# Power.net
KiCad netlist of a schematic drawn in Altium Designer
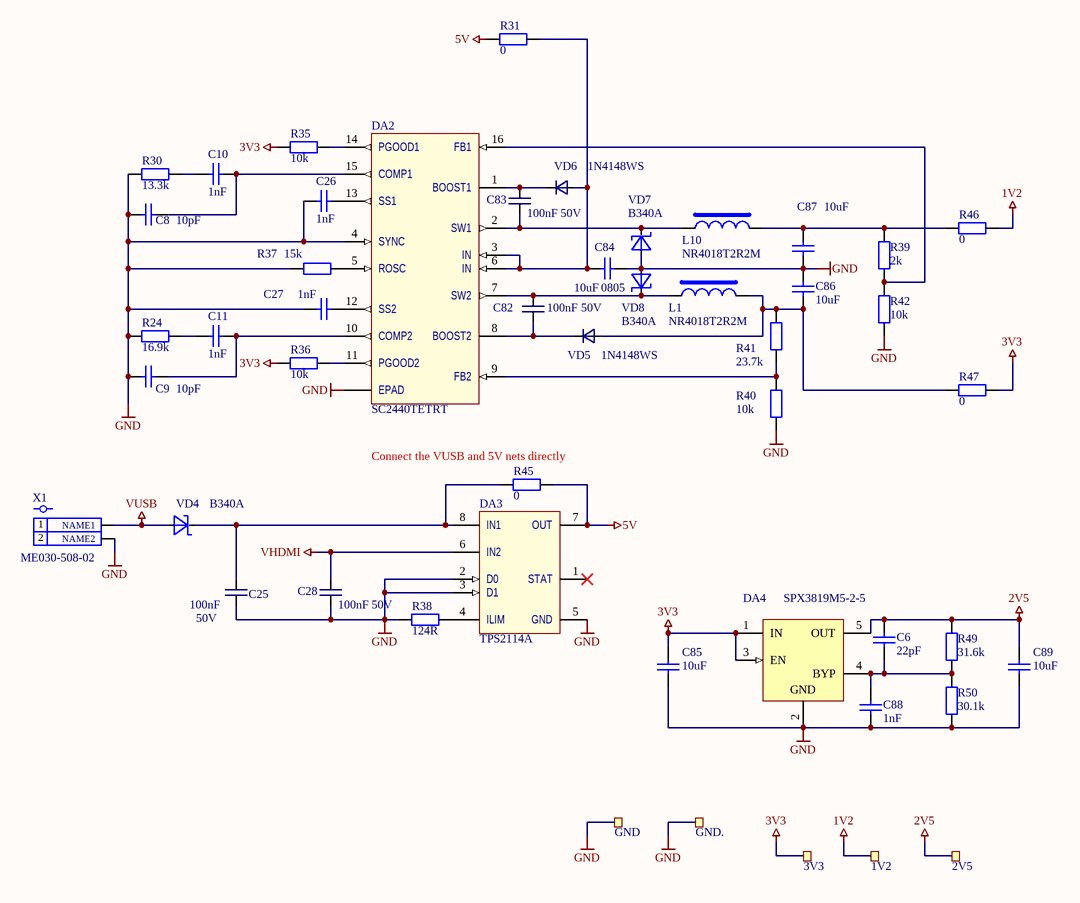
[diagram p0: Power.SchDoc]

(export (version "E")
  (design (tool "Eeschema 10.0.6"))
  (components
    (comp (ref "1V2")
      (value "TP_TH")
      (footprint "TP_TH_1MM")
      (description "Testpoint, through hole")
      (libsource (lib "LED_MAT_3") (part "TESTPAD_TH"))
    )
    (comp (ref "2V5")
      (value "Ø1.0mm,SMD")
      (footprint "TP_SMD_1MM")
      (description "circular SMD testpad 1mm")
      (libsource (lib "LED_MAT_3") (part "TESTPAD_SMD"))
    )
    (comp (ref "3V3")
      (value "TP_TH")
      (footprint "TP_TH_1MM")
      (description "Testpoint, through hole")
      (libsource (lib "LED_MAT_3") (part "TESTPAD_TH"))
    )
    (comp (ref "C6")
      (value "22pF")
      (footprint "CAPC1608L")
      (description "Capacitor ceramic")
      (fields
        (field (name "MANUFACTURER") "SAMSUNG")
        (field (name "MANUFACTURER PART NUMBER") "CL10C100JB8NNNC")
      )
      (libsource (lib "LED_MAT_3") (part "10pF / 0603 / COG / 50V"))
    )
    (comp (ref "C8")
      (value "10pF")
      (footprint "CAPC1608L")
      (description "Capacitor ceramic")
      (fields
        (field (name "MANUFACTURER") "SAMSUNG")
        (field (name "MANUFACTURER PART NUMBER") "CL10C100JB8NNNC")
      )
      (libsource (lib "LED_MAT_3") (part "10pF / 0603 / COG / 50V"))
    )
    (comp (ref "C9")
      (value "10pF")
      (footprint "CAPC1608L")
      (description "Capacitor ceramic")
      (fields
        (field (name "MANUFACTURER") "SAMSUNG")
        (field (name "MANUFACTURER PART NUMBER") "CL10C100JB8NNNC")
      )
      (libsource (lib "LED_MAT_3") (part "10pF / 0603 / COG / 50V"))
    )
    (comp (ref "C10")
      (value "1nF")
      (footprint "CAPC1608L")
      (description "Capacitor ceramic")
      (fields
        (field (name "MANUFACTURER") "MURATA")
        (field (name "MANUFACTURER PART NUMBER") "GRM1885C1H102JA01D")
      )
      (libsource (lib "LED_MAT_3") (part "1nF / 0603 / NPO / 50V"))
    )
    (comp (ref "C11")
      (value "1nF")
      (footprint "CAPC1608L")
      (description "Capacitor ceramic")
      (fields
        (field (name "MANUFACTURER") "MURATA")
        (field (name "MANUFACTURER PART NUMBER") "GRM1885C1H102JA01D")
      )
      (libsource (lib "LED_MAT_3") (part "1nF / 0603 / NPO / 50V"))
    )
    (comp (ref "C25")
      (value "100nF")
      (footprint "CAPC1608L")
      (description "Capacitor SMD")
      (fields
        (field (name "VOLTAGE") "50V")
        (field (name "TOLERANCE") "5%")
        (field (name "MANUFACTURER") "SAMSUNG")
      )
      (libsource (lib "LED_MAT_3") (part "Capacitor CC0805 100nF C0G"))
    )
    (comp (ref "C26")
      (value "1nF")
      (footprint "CAPC1608L")
      (description "Capacitor ceramic")
      (fields
        (field (name "MANUFACTURER") "MURATA")
        (field (name "MANUFACTURER PART NUMBER") "GRM1885C1H102JA01D")
      )
      (libsource (lib "LED_MAT_3") (part "1nF / 0603 / NPO / 50V"))
    )
    (comp (ref "C27")
      (value "1nF")
      (footprint "CAPC1608L")
      (description "Capacitor ceramic")
      (fields
        (field (name "MANUFACTURER") "MURATA")
        (field (name "MANUFACTURER PART NUMBER") "GRM1885C1H102JA01D")
      )
      (libsource (lib "LED_MAT_3") (part "1nF / 0603 / NPO / 50V"))
    )
    (comp (ref "C28")
      (value "100nF")
      (footprint "CAPC1608L")
      (description "Capacitor SMD")
      (fields
        (field (name "VOLTAGE") "50V")
        (field (name "TOLERANCE") "5%")
        (field (name "MANUFACTURER") "SAMSUNG")
      )
      (libsource (lib "LED_MAT_3") (part "Capacitor CC0805 100nF C0G"))
    )
    (comp (ref "C82")
      (value "100nF")
      (footprint "CAPC1608L")
      (description "Capacitor SMD")
      (fields
        (field (name "VOLTAGE") "50V")
        (field (name "TOLERANCE") "5%")
        (field (name "MANUFACTURER") "SAMSUNG")
      )
      (libsource (lib "LED_MAT_3") (part "Capacitor CC0805 100nF C0G"))
    )
    (comp (ref "C83")
      (value "100nF")
      (footprint "CAPC1608L")
      (description "Capacitor SMD")
      (fields
        (field (name "VOLTAGE") "50V")
        (field (name "TOLERANCE") "5%")
        (field (name "MANUFACTURER") "SAMSUNG")
      )
      (libsource (lib "LED_MAT_3") (part "Capacitor CC0805 100nF C0G"))
    )
    (comp (ref "C84")
      (value "10uF")
      (footprint "CAPC2012L")
      (description "Capacitor ceramic")
      (fields
        (field (name "PACKAGE") "0805")
        (field (name "VOLTAGE") "10V")
        (field (name "Comment") "10uF / 0805 /  X5R / 10V")
      )
      (libsource (lib "LED_MAT_3") (part "10uF / 0805 /  X5R / 10V"))
    )
    (comp (ref "C85")
      (value "10uF")
      (footprint "CAPC2012L")
      (description "Capacitor ceramic")
      (fields (field (name "VOLTAGE") "10V") (field (name "Comment") "10uF / 0805 /  X5R / 10V"))
      (libsource (lib "LED_MAT_3") (part "10uF / 0805 /  X5R / 10V"))
    )
    (comp (ref "C86")
      (value "10uF")
      (footprint "CAPC2012L")
      (description "Capacitor ceramic")
      (fields (field (name "VOLTAGE") "10V") (field (name "Comment") "10uF / 0805 /  X5R / 10V"))
      (libsource (lib "LED_MAT_3") (part "10uF / 0805 /  X5R / 10V"))
    )
    (comp (ref "C87")
      (value "10uF")
      (footprint "CAPC2012L")
      (description "Capacitor ceramic")
      (fields (field (name "VOLTAGE") "10V") (field (name "Comment") "10uF / 0805 /  X5R / 10V"))
      (libsource (lib "LED_MAT_3") (part "10uF / 0805 /  X5R / 10V"))
    )
    (comp (ref "C88")
      (value "1nF")
      (footprint "CAPC1608L")
      (description "Capacitor ceramic")
      (fields
        (field (name "MANUFACTURER") "MURATA")
        (field (name "MANUFACTURER PART NUMBER") "GRM1885C1H102JA01D")
      )
      (libsource (lib "LED_MAT_3") (part "1nF / 0603 / NPO / 50V"))
    )
    (comp (ref "C89")
      (value "10uF")
      (footprint "CAPC2012L")
      (description "Capacitor ceramic")
      (fields (field (name "VOLTAGE") "10V") (field (name "Comment") "10uF / 0805 /  X5R / 10V"))
      (libsource (lib "LED_MAT_3") (part "10uF / 0805 /  X5R / 10V"))
    )
    (comp (ref "DA2")
      (value "SC2440TETRT")
      (footprint "TSOP65P640X110_HS320X320-16L")
      (description "2.5 MHz Dual Switching Regulator, 2A")
      (fields (field (name "MANUFACTURER") "SEMTECH"))
      (libsource (lib "power") (part "SC2440"))
    )
    (comp (ref "DA3")
      (value "TPS2114A")
      (footprint "TSSOP65P640X120-8L")
      (description "AUTOSWITCHING POWER MUX")
      (fields (field (name "MANUFACTURER") "TI"))
      (libsource (lib "LED_MAT_3") (part "TPS2114A"))
    )
    (comp (ref "DA4")
      (value "SPX3819M5-2-5")
      (footprint "TI-DBV6_N")
      (description "500mA, Low-Noise LDO Voltage Regulator")
      (fields (field (name "MANUFACTURER") "SIPEX") (field (name "TOLERANCE") "1%"))
      (libsource (lib "LED_MAT_3") (part "SPX3819M5-2-5"))
    )
    (comp (ref "GND")
      (value "TP_TH")
      (footprint "TP_TH_1MM")
      (description "Testpoint, through hole")
      (libsource (lib "LED_MAT_3") (part "TESTPAD_TH"))
    )
    (comp (ref "GND.")
      (value "TP_TH")
      (footprint "TP_TH_1MM")
      (description "Testpoint, through hole")
      (libsource (lib "LED_MAT_3") (part "TESTPAD_TH"))
    )
    (comp (ref "L1")
      (value "NR4018T2R2M")
      (footprint "IND_CD43")
      (description "Power choke")
      (fields (field (name "MANUFACTURER") "TAIYO YUDE"))
      (libsource (lib "LED_MAT_3") (part "2.2uH Power Choke"))
    )
    (comp (ref "L10")
      (value "NR4018T2R2M")
      (footprint "IND_CD43")
      (description "Power choke")
      (fields (field (name "MANUFACTURER") "TAIYO YUDE"))
      (libsource (lib "LED_MAT_3") (part "2.2uH Power Choke"))
    )
    (comp (ref "R24")
      (value "16.9k")
      (footprint "RESC1608L")
      (description "16.9k / 1% / 0603")
      (fields
        (field (name "MANUFACTURER") "YAGEO")
        (field (name "MANUFACTURER PART NUMBER") "RC0603FR0716K9L")
      )
      (libsource (lib "LED_MAT_3") (part "16.9k / 1% / 0603"))
    )
    (comp (ref "R30")
      (value "13.3k")
      (footprint "RESC1608L")
      (description "13.3k / 1% / 0603")
      (fields
        (field (name "MANUFACTURER") "YAGEO")
        (field (name "MANUFACTURER PART NUMBER") "RC0603FR-0713K3L")
      )
      (libsource (lib "LED_MAT_3") (part "13.3k / 1% / 0603"))
    )
    (comp (ref "R31")
      (value "0")
      (footprint "RESC3216L")
      (description "0 / 1% / 0603")
      (fields
        (field (name "MANUFACTURER") "YAGEO")
        (field (name "MANUFACTURER PART NUMBER") "RC0603FR-070RL")
      )
      (libsource (lib "LED_MAT_3") (part "2k / 1% / 0603"))
    )
    (comp (ref "R35")
      (value "10k")
      (footprint "RESC1608L")
      (description "Resistor")
      (fields (field (name "TOLERANCE") "1%") (field (name "VOLTAGE") "50V"))
      (libsource (lib "") (part "10k / 1% / 0603 / TC100 / 50V / 0.1W_1"))
    )
    (comp (ref "R36")
      (value "10k")
      (footprint "RESC1608L")
      (description "Resistor")
      (fields (field (name "TOLERANCE") "1%") (field (name "VOLTAGE") "50V"))
      (libsource (lib "") (part "10k / 1% / 0603 / TC100 / 50V / 0.1W_1"))
    )
    (comp (ref "R37")
      (value "15k")
      (footprint "RESC1608L")
      (description "15k / 1% / 0603")
      (fields
        (field (name "MANUFACTURER") "YAGEO")
        (field (name "MANUFACTURER PART NUMBER") "RC0603FR-0715KL")
      )
      (libsource (lib "LED_MAT_3") (part "15k / 1% / 0603"))
    )
    (comp (ref "R38")
      (value "124R")
      (footprint "RESC1608L")
      (description "124R / 1% / 0603")
      (fields
        (field (name "MANUFACTURER") "PANASONIC")
        (field (name "MANUFACTURER PART NUMBER") "ERJ-3EKF1240V")
      )
      (libsource (lib "") (part "124R / 1% / 0603_1"))
    )
    (comp (ref "R39")
      (value "2k")
      (footprint "RESC1608L")
      (description "2k / 1% / 0603")
      (fields
        (field (name "MANUFACTURER") "YAGEO")
        (field (name "MANUFACTURER PART NUMBER") "RC0603FR-072KL")
      )
      (libsource (lib "") (part "2k / 1% / 0603_1"))
    )
    (comp (ref "R40")
      (value "10k")
      (footprint "RESC1608L")
      (description "Resistor")
      (fields (field (name "TOLERANCE") "1%") (field (name "VOLTAGE") "50V"))
      (libsource (lib "LED_MAT_3") (part "10k / 1% / 0603 / TC100 / 50V / 0.1W"))
    )
    (comp (ref "R41")
      (value "23.7k")
      (footprint "RESC1608L")
      (description "23.7k / 1% / 0603")
      (fields
        (field (name "MANUFACTURER") "YAGEO")
        (field (name "MANUFACTURER PART NUMBER") "RC0603FR-0723K7L")
      )
      (libsource (lib "LED_MAT_3") (part "23.7k / 1% / 0603"))
    )
    (comp (ref "R42")
      (value "10k")
      (footprint "RESC1608L")
      (description "Resistor")
      (fields (field (name "TOLERANCE") "1%") (field (name "VOLTAGE") "50V"))
      (libsource (lib "LED_MAT_3") (part "10k / 1% / 0603 / TC100 / 50V / 0.1W"))
    )
    (comp (ref "R45")
      (value "0")
      (footprint "RESC1608L")
      (description "0 / 1% / 0603")
      (fields
        (field (name "MANUFACTURER") "YAGEO")
        (field (name "MANUFACTURER PART NUMBER") "RC0603FR-070RL")
      )
      (libsource (lib "LED_MAT_3") (part "2k / 1% / 0603"))
    )
    (comp (ref "R46")
      (value "0")
      (footprint "RESC1608L")
      (description "0 / 1% / 0603")
      (fields
        (field (name "MANUFACTURER") "YAGEO")
        (field (name "MANUFACTURER PART NUMBER") "RC0603FR-070RL")
      )
      (libsource (lib "LED_MAT_3") (part "2k / 1% / 0603"))
    )
    (comp (ref "R47")
      (value "0")
      (footprint "RESC1608L")
      (description "0 / 1% / 0603")
      (fields
        (field (name "MANUFACTURER") "YAGEO")
        (field (name "MANUFACTURER PART NUMBER") "RC0603FR-070RL")
      )
      (libsource (lib "LED_MAT_3") (part "2k / 1% / 0603"))
    )
    (comp (ref "R49")
      (value "31.6k")
      (footprint "RESC1608L")
      (description "31.6k / 1% / 0603")
      (fields
        (field (name "MANUFACTURER") "YAGEO")
        (field (name "MANUFACTURER PART NUMBER") "RC0603FR-0739RL")
      )
      (libsource (lib "LED_MAT_3") (part "39R / 1% / 0603"))
    )
    (comp (ref "R50")
      (value "30.1k")
      (footprint "RESC1608L")
      (description "30.1k / 1% / 0603")
      (fields
        (field (name "MANUFACTURER") "PANASONIC")
        (field (name "MANUFACTURER PART NUMBER") "ERJ-3EKF1240V")
      )
      (libsource (lib "LED_MAT_3") (part "124R / 1% / 0603"))
    )
    (comp (ref "VD4")
      (value "B340A")
      (footprint "DO-214AC(SMA)")
      (description "Shottky restifiers, 2A, SMA Package")
      (fields (field (name "MANUFACTURER") "DIODES") (field (name "VOLTAGE") "40V"))
      (libsource (lib "LED_MAT_3") (part "B360A"))
    )
    (comp (ref "VD5")
      (value "1N4148WS")
      (footprint "SOD123")
      (description "Fast switching diode")
      (fields
        (field (name "MANUFACTURER") "VISHAY")
        (field (name "MANUFACTURER PART NUMBER") "1N4148WS-E3-08")
      )
      (libsource (lib "LED_MAT_3") (part "1N4148W"))
    )
    (comp (ref "VD6")
      (value "1N4148WS")
      (footprint "SOD123")
      (description "Fast switching diode")
      (fields
        (field (name "MANUFACTURER") "VISHAY")
        (field (name "MANUFACTURER PART NUMBER") "1N4148WS-E3-08")
      )
      (libsource (lib "LED_MAT_3") (part "1N4148W"))
    )
    (comp (ref "VD7")
      (value "B340A")
      (footprint "DO-214AC(SMA)")
      (description "Shottky restifiers, 2A, SMA Package")
      (fields (field (name "MANUFACTURER") "DIODES") (field (name "VOLTAGE") "40V"))
      (libsource (lib "LED_MAT_3") (part "B360A"))
    )
    (comp (ref "VD8")
      (value "B340A")
      (footprint "DO-214AC(SMA)")
      (description "Shottky restifiers, 2A, SMA Package")
      (fields (field (name "MANUFACTURER") "DIODES") (field (name "VOLTAGE") "40V"))
      (libsource (lib "LED_MAT_3") (part "B360A"))
    )
    (comp (ref "X1")
      (value "ME030-508-02")
      (footprint "ME030-508-02")
      (description "2-pin HPWR connector")
      (fields (field (name "MANUFACTURER") "DECA SWITC"))
      (libsource (lib "LED_MAT_3") (part "CON2_TermBlock"))
    )
  )
  (nets
    (net (code "1") (name "1V2") (class "Default")
      (node (ref "1V2") (pin "1") (pinfunction "1_1") (pintype "passive"))
      (node (ref "R46") (pin "2") (pinfunction "2_2") (pintype "passive"))
    )
    (net (code "2") (name "2V5") (class "Default")
      (node (ref "2V5") (pin "1") (pinfunction "1_1") (pintype "passive"))
      (node (ref "C6") (pin "1") (pinfunction "1_1") (pintype "passive"))
      (node (ref "C89") (pin "2") (pinfunction "2_2") (pintype "passive"))
      (node (ref "DA4") (pin "5") (pinfunction "OUT_5") (pintype "power_in"))
      (node (ref "R49") (pin "2") (pinfunction "2_2") (pintype "passive"))
    )
    (net (code "3") (name "3V3") (class "Default")
      (node (ref "3V3") (pin "1") (pinfunction "1_1") (pintype "passive"))
      (node (ref "C85") (pin "2") (pinfunction "2_2") (pintype "passive"))
      (node (ref "DA4") (pin "1") (pinfunction "IN_1") (pintype "power_in"))
      (node (ref "DA4") (pin "3") (pinfunction "EN_3") (pintype "input"))
      (node (ref "R35") (pin "1") (pinfunction "1_1") (pintype "passive"))
      (node (ref "R36") (pin "1") (pinfunction "1_1") (pintype "passive"))
      (node (ref "R47") (pin "2") (pinfunction "2_2") (pintype "passive"))
    )
    (net (code "4") (name "5V") (class "Default")
      (node (ref "DA3") (pin "7") (pinfunction "OUT_7") (pintype "power_in"))
      (node (ref "R31") (pin "1") (pinfunction "1_1") (pintype "passive"))
      (node (ref "R45") (pin "2") (pinfunction "2_2") (pintype "passive"))
    )
    (net (code "5") (name "GND") (class "Default")
      (node (ref "C25") (pin "2") (pintype "passive"))
      (node (ref "C26") (pin "1") (pinfunction "1_1") (pintype "passive"))
      (node (ref "C27") (pin "1") (pinfunction "1_1") (pintype "passive"))
      (node (ref "C28") (pin "1") (pintype "passive"))
      (node (ref "C8") (pin "2") (pinfunction "2_2") (pintype "passive"))
      (node (ref "C84") (pin "1") (pinfunction "1_1") (pintype "passive"))
      (node (ref "C85") (pin "1") (pinfunction "1_1") (pintype "passive"))
      (node (ref "C86") (pin "1") (pinfunction "1_1") (pintype "passive"))
      (node (ref "C87") (pin "1") (pinfunction "1_1") (pintype "passive"))
      (node (ref "C88") (pin "1") (pinfunction "1_1") (pintype "passive"))
      (node (ref "C89") (pin "1") (pinfunction "1_1") (pintype "passive"))
      (node (ref "C9") (pin "2") (pinfunction "2_2") (pintype "passive"))
      (node (ref "DA2") (pin "4") (pinfunction "SYNC_4") (pintype "input"))
      (node (ref "DA2") (pin "EPAD") (pinfunction "EPAD_EPAD") (pintype "power_in"))
      (node (ref "DA3") (pin "2") (pinfunction "D0_2") (pintype "input"))
      (node (ref "DA3") (pin "3") (pinfunction "D1_3") (pintype "input"))
      (node (ref "DA3") (pin "5") (pinfunction "GND_5") (pintype "power_in"))
      (node (ref "DA4") (pin "2") (pinfunction "GND_2") (pintype "power_in"))
      (node (ref "GND") (pin "1") (pinfunction "1_1") (pintype "passive"))
      (node (ref "GND.") (pin "1") (pinfunction "1_1") (pintype "passive"))
      (node (ref "R24") (pin "1") (pinfunction "1_1") (pintype "passive"))
      (node (ref "R30") (pin "1") (pinfunction "1_1") (pintype "passive"))
      (node (ref "R37") (pin "1") (pinfunction "1_1") (pintype "passive"))
      (node (ref "R38") (pin "2") (pinfunction "2_2") (pintype "passive"))
      (node (ref "R40") (pin "2") (pinfunction "2_2") (pintype "passive"))
      (node (ref "R42") (pin "2") (pinfunction "2_2") (pintype "passive"))
      (node (ref "R50") (pin "1") (pinfunction "1_1") (pintype "passive"))
      (node (ref "VD7") (pin "1") (pinfunction "1_1") (pintype "passive"))
      (node (ref "VD8") (pin "1") (pinfunction "1_1") (pintype "passive"))
      (node (ref "X1") (pin "2") (pinfunction "NAME2_2") (pintype "passive"))
    )
    (net (code "6") (name "Net-(C10-Pad2)") (class "Default")
      (node (ref "C10") (pin "2") (pinfunction "2_2") (pintype "passive"))
      (node (ref "R30") (pin "2") (pinfunction "2_2") (pintype "passive"))
    )
    (net (code "7") (name "Net-(C11-Pad2)") (class "Default")
      (node (ref "C11") (pin "2") (pinfunction "2_2") (pintype "passive"))
      (node (ref "R24") (pin "2") (pinfunction "2_2") (pintype "passive"))
    )
    (net (code "8") (name "Net-(C84-Pad2)") (class "Default")
      (node (ref "C84") (pin "2") (pinfunction "2_2") (pintype "passive"))
      (node (ref "DA2") (pin "3") (pinfunction "IN_3") (pintype "input"))
      (node (ref "DA2") (pin "6") (pinfunction "IN_6") (pintype "input"))
      (node (ref "R31") (pin "2") (pinfunction "2_2") (pintype "passive"))
      (node (ref "VD6") (pin "1") (pinfunction "1_1") (pintype "passive"))
    )
    (net (code "9") (name "Net-(C86-Pad2)") (class "Default")
      (node (ref "C86") (pin "2") (pinfunction "2_2") (pintype "passive"))
      (node (ref "L1") (pin "2") (pinfunction "2_2") (pintype "passive"))
      (node (ref "R41") (pin "1") (pinfunction "1_1") (pintype "passive"))
      (node (ref "R47") (pin "1") (pinfunction "1_1") (pintype "passive"))
      (node (ref "VD5") (pin "1") (pinfunction "1_1") (pintype "passive"))
    )
    (net (code "10") (name "Net-(C87-Pad2)") (class "Default")
      (node (ref "C87") (pin "2") (pinfunction "2_2") (pintype "passive"))
      (node (ref "L10") (pin "2") (pinfunction "2_2") (pintype "passive"))
      (node (ref "R39") (pin "1") (pinfunction "1_1") (pintype "passive"))
      (node (ref "R46") (pin "1") (pinfunction "1_1") (pintype "passive"))
    )
    (net (code "11") (name "Net-(DA2-BOOST1)") (class "Default")
      (node (ref "C83") (pin "2") (pintype "passive"))
      (node (ref "DA2") (pin "1") (pinfunction "BOOST1_1") (pintype "power_in"))
      (node (ref "VD6") (pin "2") (pinfunction "2_2") (pintype "passive"))
    )
    (net (code "12") (name "Net-(DA2-BOOST2)") (class "Default")
      (node (ref "C82") (pin "1") (pintype "passive"))
      (node (ref "DA2") (pin "8") (pinfunction "BOOST2_8") (pintype "power_in"))
      (node (ref "VD5") (pin "2") (pinfunction "2_2") (pintype "passive"))
    )
    (net (code "13") (name "Net-(DA2-COMP1)") (class "Default")
      (node (ref "C10") (pin "1") (pinfunction "1_1") (pintype "passive"))
      (node (ref "C8") (pin "1") (pinfunction "1_1") (pintype "passive"))
      (node (ref "DA2") (pin "15") (pinfunction "COMP1_15") (pintype "output"))
    )
    (net (code "14") (name "Net-(DA2-COMP2)") (class "Default")
      (node (ref "C11") (pin "1") (pinfunction "1_1") (pintype "passive"))
      (node (ref "C9") (pin "1") (pinfunction "1_1") (pintype "passive"))
      (node (ref "DA2") (pin "10") (pinfunction "COMP2_10") (pintype "output"))
    )
    (net (code "15") (name "Net-(DA2-FB1)") (class "Default")
      (node (ref "DA2") (pin "16") (pinfunction "FB1_16") (pintype "input"))
      (node (ref "R39") (pin "2") (pinfunction "2_2") (pintype "passive"))
      (node (ref "R42") (pin "1") (pinfunction "1_1") (pintype "passive"))
    )
    (net (code "16") (name "Net-(DA2-FB2)") (class "Default")
      (node (ref "DA2") (pin "9") (pinfunction "FB2_9") (pintype "input"))
      (node (ref "R40") (pin "1") (pinfunction "1_1") (pintype "passive"))
      (node (ref "R41") (pin "2") (pinfunction "2_2") (pintype "passive"))
    )
    (net (code "17") (name "Net-(DA2-PGOOD1)") (class "Default")
      (node (ref "DA2") (pin "14") (pinfunction "PGOOD1_14") (pintype "output"))
      (node (ref "R35") (pin "2") (pinfunction "2_2") (pintype "passive"))
    )
    (net (code "18") (name "Net-(DA2-PGOOD2)") (class "Default")
      (node (ref "DA2") (pin "11") (pinfunction "PGOOD2_11") (pintype "output"))
      (node (ref "R36") (pin "2") (pinfunction "2_2") (pintype "passive"))
    )
    (net (code "19") (name "Net-(DA2-ROSC)") (class "Default")
      (node (ref "DA2") (pin "5") (pinfunction "ROSC_5") (pintype "input"))
      (node (ref "R37") (pin "2") (pinfunction "2_2") (pintype "passive"))
    )
    (net (code "20") (name "Net-(DA2-SS1)") (class "Default")
      (node (ref "C26") (pin "2") (pinfunction "2_2") (pintype "passive"))
      (node (ref "DA2") (pin "13") (pinfunction "SS1_13") (pintype "output"))
    )
    (net (code "21") (name "Net-(DA2-SS2)") (class "Default")
      (node (ref "C27") (pin "2") (pinfunction "2_2") (pintype "passive"))
      (node (ref "DA2") (pin "12") (pinfunction "SS2_12") (pintype "output"))
    )
    (net (code "22") (name "Net-(DA2-SW1)") (class "Default")
      (node (ref "C83") (pin "1") (pintype "passive"))
      (node (ref "DA2") (pin "2") (pinfunction "SW1_2") (pintype "output"))
      (node (ref "L10") (pin "1") (pinfunction "1_1") (pintype "passive"))
      (node (ref "VD7") (pin "2") (pinfunction "2_2") (pintype "passive"))
    )
    (net (code "23") (name "Net-(DA2-SW2)") (class "Default")
      (node (ref "C82") (pin "2") (pintype "passive"))
      (node (ref "DA2") (pin "7") (pinfunction "SW2_7") (pintype "output"))
      (node (ref "L1") (pin "1") (pinfunction "1_1") (pintype "passive"))
      (node (ref "VD8") (pin "2") (pinfunction "2_2") (pintype "passive"))
    )
    (net (code "24") (name "Net-(DA3-ILIM)") (class "Default")
      (node (ref "DA3") (pin "4") (pinfunction "ILIM_4") (pintype "passive"))
      (node (ref "R38") (pin "1") (pinfunction "1_1") (pintype "passive"))
    )
    (net (code "25") (name "Net-(DA3-IN1)") (class "Default")
      (node (ref "C25") (pin "1") (pintype "passive"))
      (node (ref "DA3") (pin "8") (pinfunction "IN1_8") (pintype "power_in"))
      (node (ref "R45") (pin "1") (pinfunction "1_1") (pintype "passive"))
      (node (ref "VD4") (pin "2") (pinfunction "2_2") (pintype "passive"))
    )
    (net (code "26") (name "Net-(DA4-BYP)") (class "Default")
      (node (ref "C6") (pin "2") (pinfunction "2_2") (pintype "passive"))
      (node (ref "C88") (pin "2") (pinfunction "2_2") (pintype "passive"))
      (node (ref "DA4") (pin "4") (pinfunction "BYP_4") (pintype "passive"))
      (node (ref "R49") (pin "1") (pinfunction "1_1") (pintype "passive"))
      (node (ref "R50") (pin "2") (pinfunction "2_2") (pintype "passive"))
    )
    (net (code "27") (name "VHDMI") (class "Default")
      (node (ref "C28") (pin "2") (pintype "passive"))
      (node (ref "DA3") (pin "6") (pinfunction "IN2_6") (pintype "power_in"))
    )
    (net (code "28") (name "VUSB") (class "Default")
      (node (ref "VD4") (pin "1") (pinfunction "1_1") (pintype "passive"))
      (node (ref "X1") (pin "1") (pinfunction "NAME1_1") (pintype "passive"))
    )
    (net (code "29") (name "unconnected-(DA3-STAT-Pad1)") (class "Default")
      (node (ref "DA3") (pin "1") (pinfunction "STAT_1") (pintype "open_collector+no_connect"))
    )
  )
)
